# main.net
KiCad netlist of a schematic drawn in EAGLE
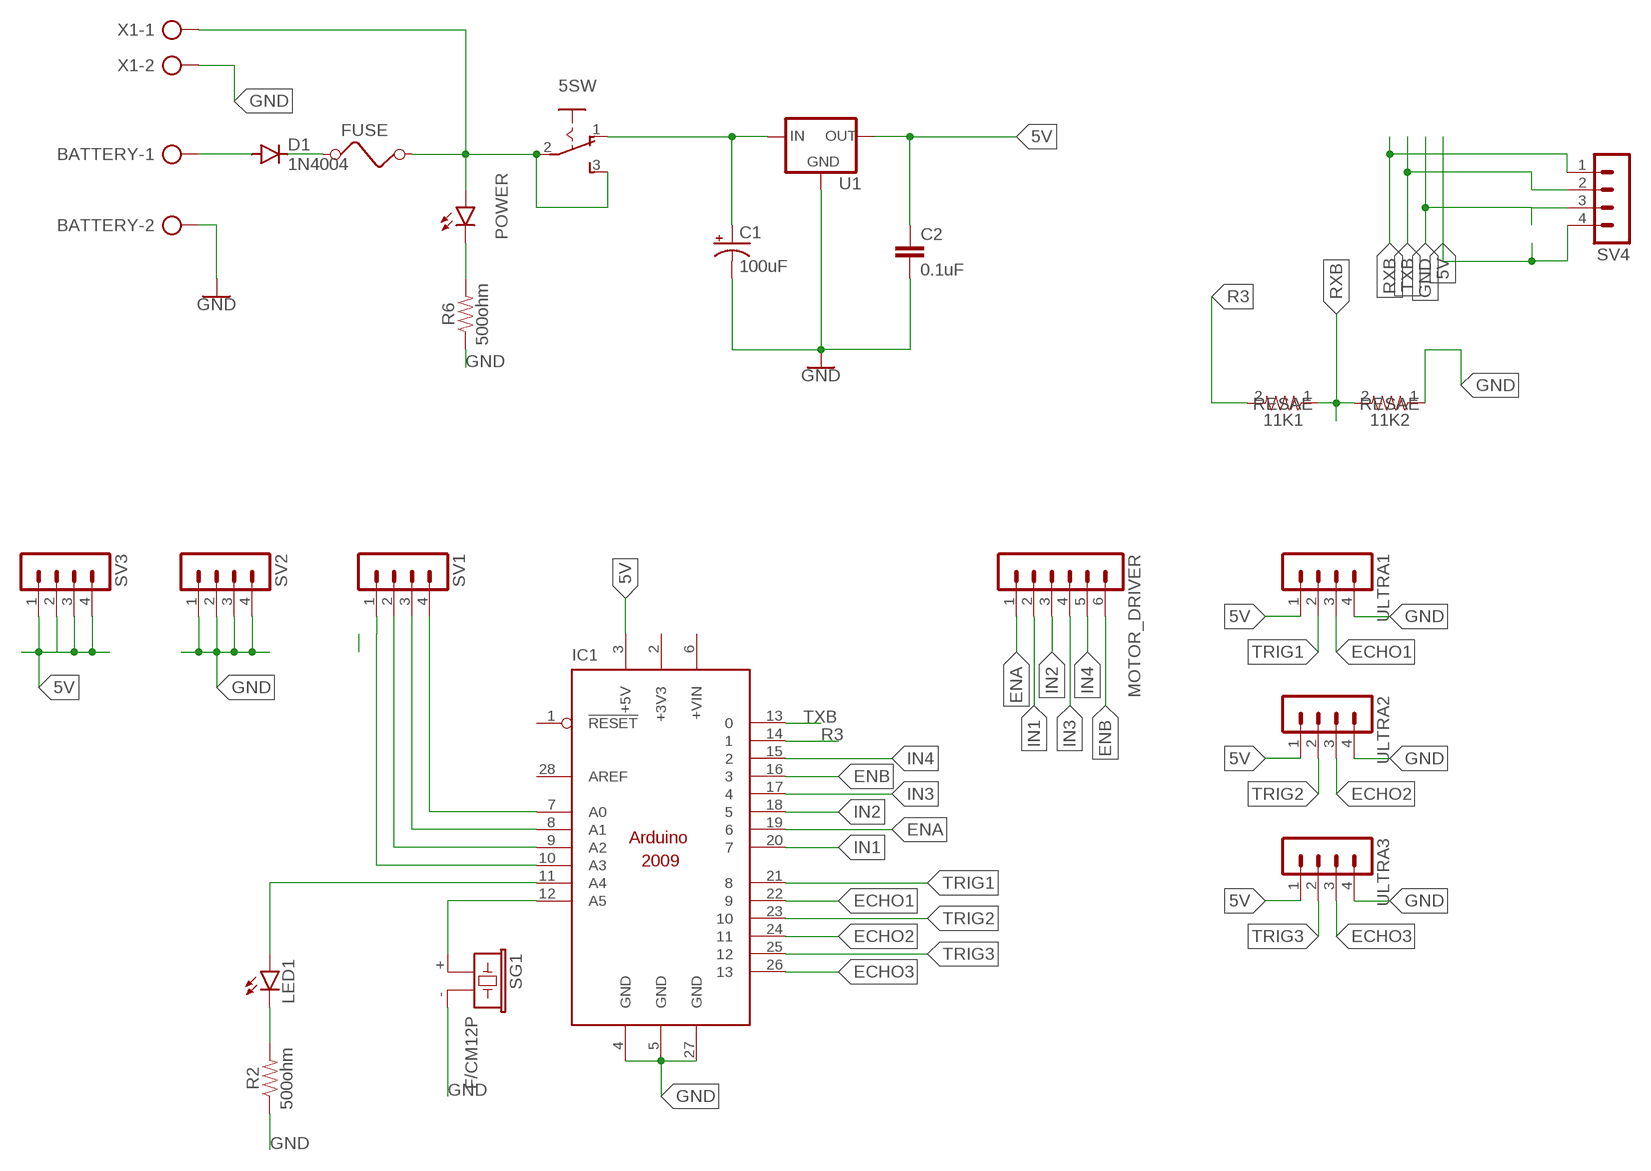
[diagram p0: schematic, sheet 1]

(export (version "E")
  (design (tool "Eeschema 10.0.6"))
  (components
    (comp (ref "5SW")
      (value "255SB")
      (footprint "eagle-import:255SB")
      (libsource (lib "eagle-import") (part "255SB"))
    )
    (comp (ref "11K1")
      (value "RESAE")
      (footprint "eagle-import:RESAD846W63L520D250B")
      (libsource (lib "eagle-import") (part "RESAE"))
    )
    (comp (ref "11K2")
      (value "RESAE")
      (footprint "eagle-import:RESAD846W63L520D250B")
      (libsource (lib "eagle-import") (part "RESAE"))
    )
    (comp (ref "BATTERY")
      (value "AK500/2-H")
      (footprint "eagle-import:AK500_2-H")
      (libsource (lib "eagle-import") (part "AK500/2-H"))
    )
    (comp (ref "C1")
      (value "100uF")
      (footprint "eagle-import:CPOL-RADIAL-2.5MM-6.5MM")
      (libsource (lib "eagle-import") (part "100UF-POLAR-RADIAL-2.5MM-25V-20%"))
    )
    (comp (ref "C2")
      (value "0.1uF")
      (footprint "eagle-import:CAP-PTH-SMALL-KIT")
      (libsource (lib "eagle-import") (part "0.1UF-KIT-EZ-50V-20%"))
    )
    (comp (ref "D1")
      (value "1N4004")
      (footprint "eagle-import:DO41-10")
      (libsource (lib "eagle-import") (part "1N4004"))
    )
    (comp (ref "FUSE")
      (value "FUSE")
      (footprint "eagle-import:FUSE")
      (libsource (lib "eagle-import") (part "FUSE"))
    )
    (comp (ref "IC1")
      (value "ARDUINO2009_10")
      (footprint "eagle-import:ARDUINO2009")
      (libsource (lib "eagle-import") (part "ARDUINO2009_10"))
    )
    (comp (ref "LED1")
      (value "LED10MM")
      (footprint "eagle-import:LED10MM")
      (libsource (lib "eagle-import") (part "LED10MM"))
    )
    (comp (ref "MOTOR_DRIVER")
      (value "MA06-1")
      (footprint "eagle-import:MA06-1")
      (libsource (lib "eagle-import") (part "MA06-1"))
    )
    (comp (ref "POWER")
      (value "LED3MM")
      (footprint "eagle-import:LED3MM")
      (libsource (lib "eagle-import") (part "LED3MM"))
    )
    (comp (ref "R2")
      (value "500ohm")
      (footprint "eagle-import:AXIAL-0.3")
      (libsource (lib "eagle-import") (part "10MOHM-HORIZ-1/4W-5%"))
    )
    (comp (ref "R6")
      (value "500ohm")
      (footprint "eagle-import:AXIAL-0.3")
      (libsource (lib "eagle-import") (part "10MOHM-HORIZ-1/4W-5%"))
    )
    (comp (ref "SG1")
      (value "F/CM12P")
      (footprint "eagle-import:F_CM12P")
      (libsource (lib "eagle-import") (part "F/CM12P"))
    )
    (comp (ref "SV1")
      (value "MA04-1")
      (footprint "eagle-import:MA04-1")
      (libsource (lib "eagle-import") (part "MA04-1"))
    )
    (comp (ref "SV2")
      (value "MA04-1")
      (footprint "eagle-import:MA04-1")
      (libsource (lib "eagle-import") (part "MA04-1"))
    )
    (comp (ref "SV3")
      (value "MA04-1")
      (footprint "eagle-import:MA04-1")
      (libsource (lib "eagle-import") (part "MA04-1"))
    )
    (comp (ref "SV4")
      (value "MA04-1")
      (footprint "eagle-import:MA04-1")
      (libsource (lib "eagle-import") (part "MA04-1"))
    )
    (comp (ref "U1")
      (value "78XXS")
      (footprint "eagle-import:78XXS")
      (libsource (lib "eagle-import") (part "78XXS"))
    )
    (comp (ref "ULTRA1")
      (value "MA04-1")
      (footprint "eagle-import:MA04-1")
      (libsource (lib "eagle-import") (part "MA04-1"))
    )
    (comp (ref "ULTRA2")
      (value "MA04-1")
      (footprint "eagle-import:MA04-1")
      (libsource (lib "eagle-import") (part "MA04-1"))
    )
    (comp (ref "ULTRA3")
      (value "MA04-1")
      (footprint "eagle-import:MA04-1")
      (libsource (lib "eagle-import") (part "MA04-1"))
    )
    (comp (ref "X1")
      (value "AK500/2-H")
      (footprint "eagle-import:AK500_2-H")
      (libsource (lib "eagle-import") (part "AK500/2-H"))
    )
  )
  (nets
    (net (code "1") (name "/+3V3") (class "Default")
      (node (ref "IC1") (pin "2") (pinfunction "+3V3_2") (pintype "power_in"))
    )
    (net (code "2") (name "5V") (class "Default")
      (node (ref "C2") (pin "1") (pinfunction "1_1") (pintype "passive"))
      (node (ref "IC1") (pin "3") (pinfunction "+5V_3") (pintype "power_in"))
      (node (ref "SV3") (pin "1") (pinfunction "1_1") (pintype "passive"))
      (node (ref "SV3") (pin "2") (pinfunction "2_2") (pintype "passive"))
      (node (ref "SV3") (pin "3") (pinfunction "3_3") (pintype "passive"))
      (node (ref "SV3") (pin "4") (pinfunction "4_4") (pintype "passive"))
      (node (ref "SV4") (pin "4") (pinfunction "4_4") (pintype "passive"))
      (node (ref "U1") (pin "OUT") (pinfunction "OUT_OUT") (pintype "passive"))
      (node (ref "ULTRA1") (pin "1") (pinfunction "1_1") (pintype "passive"))
      (node (ref "ULTRA2") (pin "1") (pinfunction "1_1") (pintype "passive"))
      (node (ref "ULTRA3") (pin "1") (pinfunction "1_1") (pintype "passive"))
    )
    (net (code "3") (name "ECHO1") (class "Default")
      (node (ref "IC1") (pin "22") (pinfunction "9_22") (pintype "bidirectional"))
      (node (ref "ULTRA1") (pin "3") (pinfunction "3_3") (pintype "passive"))
    )
    (net (code "4") (name "ECHO2") (class "Default")
      (node (ref "IC1") (pin "24") (pinfunction "11_24") (pintype "bidirectional"))
      (node (ref "ULTRA2") (pin "3") (pinfunction "3_3") (pintype "passive"))
    )
    (net (code "5") (name "ECHO3") (class "Default")
      (node (ref "IC1") (pin "26") (pinfunction "13_26") (pintype "bidirectional"))
      (node (ref "ULTRA3") (pin "3") (pinfunction "3_3") (pintype "passive"))
    )
    (net (code "6") (name "ENA") (class "Default")
      (node (ref "IC1") (pin "19") (pinfunction "6_19") (pintype "bidirectional"))
      (node (ref "MOTOR_DRIVER") (pin "1") (pinfunction "1_1") (pintype "passive"))
    )
    (net (code "7") (name "ENB") (class "Default")
      (node (ref "IC1") (pin "16") (pinfunction "3_16") (pintype "bidirectional"))
      (node (ref "MOTOR_DRIVER") (pin "6") (pinfunction "6_6") (pintype "passive"))
    )
    (net (code "8") (name "GND") (class "Default")
      (node (ref "11K2") (pin "1") (pinfunction "1_1") (pintype "passive"))
      (node (ref "BATTERY") (pin "2") (pinfunction "KL_2") (pintype "passive"))
      (node (ref "C1") (pin "2") (pinfunction "-_2") (pintype "passive"))
      (node (ref "C2") (pin "2") (pinfunction "2_2") (pintype "passive"))
      (node (ref "IC1") (pin "27") (pinfunction "GND_27") (pintype "power_in"))
      (node (ref "IC1") (pin "4") (pinfunction "GND_4") (pintype "power_in"))
      (node (ref "IC1") (pin "5") (pinfunction "GND_5") (pintype "power_in"))
      (node (ref "R2") (pin "P$1") (pinfunction "1_P$1") (pintype "passive"))
      (node (ref "R6") (pin "P$1") (pinfunction "1_P$1") (pintype "passive"))
      (node (ref "SG1") (pin "-") (pinfunction "2_-") (pintype "passive"))
      (node (ref "SV2") (pin "1") (pinfunction "1_1") (pintype "passive"))
      (node (ref "SV2") (pin "2") (pinfunction "2_2") (pintype "passive"))
      (node (ref "SV2") (pin "3") (pinfunction "3_3") (pintype "passive"))
      (node (ref "SV2") (pin "4") (pinfunction "4_4") (pintype "passive"))
      (node (ref "SV4") (pin "3") (pinfunction "3_3") (pintype "passive"))
      (node (ref "U1") (pin "GND") (pinfunction "GND_GND") (pintype "input"))
      (node (ref "ULTRA1") (pin "4") (pinfunction "4_4") (pintype "passive"))
      (node (ref "ULTRA2") (pin "4") (pinfunction "4_4") (pintype "passive"))
      (node (ref "ULTRA3") (pin "4") (pinfunction "4_4") (pintype "passive"))
      (node (ref "X1") (pin "2") (pinfunction "KL_2") (pintype "passive"))
    )
    (net (code "9") (name "IN1") (class "Default")
      (node (ref "IC1") (pin "20") (pinfunction "7_20") (pintype "bidirectional"))
      (node (ref "MOTOR_DRIVER") (pin "2") (pinfunction "2_2") (pintype "passive"))
    )
    (net (code "10") (name "IN2") (class "Default")
      (node (ref "IC1") (pin "18") (pinfunction "5_18") (pintype "bidirectional"))
      (node (ref "MOTOR_DRIVER") (pin "3") (pinfunction "3_3") (pintype "passive"))
    )
    (net (code "11") (name "IN3") (class "Default")
      (node (ref "IC1") (pin "17") (pinfunction "4_17") (pintype "bidirectional"))
      (node (ref "MOTOR_DRIVER") (pin "4") (pinfunction "4_4") (pintype "passive"))
    )
    (net (code "12") (name "IN4") (class "Default")
      (node (ref "IC1") (pin "15") (pinfunction "2_15") (pintype "bidirectional"))
      (node (ref "MOTOR_DRIVER") (pin "5") (pinfunction "5_5") (pintype "passive"))
    )
    (net (code "13") (name "Net-(5SW-O)") (class "Default")
      (node (ref "5SW") (pin "1") (pinfunction "O_1") (pintype "passive"))
      (node (ref "C1") (pin "1") (pinfunction "+_1") (pintype "passive"))
      (node (ref "U1") (pin "IN") (pinfunction "IN_IN") (pintype "input"))
    )
    (net (code "14") (name "Net-(5SW-P)") (class "Default")
      (node (ref "5SW") (pin "2") (pinfunction "P_2") (pintype "passive"))
      (node (ref "5SW") (pin "3") (pinfunction "S_3") (pintype "passive"))
      (node (ref "FUSE") (pin "2") (pinfunction "2_2") (pintype "passive"))
      (node (ref "POWER") (pin "A") (pinfunction "A_A") (pintype "passive"))
      (node (ref "X1") (pin "1") (pinfunction "KL_1") (pintype "passive"))
    )
    (net (code "15") (name "Net-(BATTERYA-KL)") (class "Default")
      (node (ref "BATTERY") (pin "1") (pinfunction "KL_1") (pintype "passive"))
      (node (ref "D1") (pin "A") (pinfunction "A_A") (pintype "passive"))
    )
    (net (code "16") (name "Net-(D1-PadC)") (class "Default")
      (node (ref "D1") (pin "C") (pinfunction "C_C") (pintype "passive"))
      (node (ref "FUSE") (pin "1") (pinfunction "1_1") (pintype "passive"))
    )
    (net (code "17") (name "Net-(IC1-A0)") (class "Default")
      (node (ref "IC1") (pin "7") (pinfunction "A0_7") (pintype "bidirectional"))
      (node (ref "SV1") (pin "4") (pinfunction "4_4") (pintype "passive"))
    )
    (net (code "18") (name "Net-(IC1-A1)") (class "Default")
      (node (ref "IC1") (pin "8") (pinfunction "A1_8") (pintype "bidirectional"))
      (node (ref "SV1") (pin "3") (pinfunction "3_3") (pintype "passive"))
    )
    (net (code "19") (name "Net-(IC1-A2)") (class "Default")
      (node (ref "IC1") (pin "9") (pinfunction "A2_9") (pintype "bidirectional"))
      (node (ref "SV1") (pin "2") (pinfunction "2_2") (pintype "passive"))
    )
    (net (code "20") (name "Net-(IC1-A3)") (class "Default")
      (node (ref "IC1") (pin "10") (pinfunction "A3_10") (pintype "bidirectional"))
      (node (ref "SV1") (pin "1") (pinfunction "1_1") (pintype "passive"))
    )
    (net (code "21") (name "Net-(IC1-A4)") (class "Default")
      (node (ref "IC1") (pin "11") (pinfunction "A4_11") (pintype "bidirectional"))
      (node (ref "LED1") (pin "A") (pinfunction "A_A") (pintype "passive"))
    )
    (net (code "22") (name "Net-(IC1-A5)") (class "Default")
      (node (ref "IC1") (pin "12") (pinfunction "A5_12") (pintype "bidirectional"))
      (node (ref "SG1") (pin "+") (pinfunction "1_+") (pintype "passive"))
    )
    (net (code "23") (name "Net-(LED1-C)") (class "Default")
      (node (ref "LED1") (pin "K") (pinfunction "C_K") (pintype "passive"))
      (node (ref "R2") (pin "P$2") (pinfunction "2_P$2") (pintype "passive"))
    )
    (net (code "24") (name "Net-(POWER-C)") (class "Default")
      (node (ref "POWER") (pin "K") (pinfunction "C_K") (pintype "passive"))
      (node (ref "R6") (pin "P$2") (pinfunction "2_P$2") (pintype "passive"))
    )
    (net (code "25") (name "R3") (class "Default")
      (node (ref "11K1") (pin "2") (pinfunction "2_2") (pintype "passive"))
      (node (ref "IC1") (pin "14") (pinfunction "1_14") (pintype "bidirectional"))
    )
    (net (code "26") (name "RXB") (class "Default")
      (node (ref "11K1") (pin "1") (pinfunction "1_1") (pintype "passive"))
      (node (ref "11K2") (pin "2") (pinfunction "2_2") (pintype "passive"))
      (node (ref "SV4") (pin "1") (pinfunction "1_1") (pintype "passive"))
    )
    (net (code "27") (name "TRIG1") (class "Default")
      (node (ref "IC1") (pin "21") (pinfunction "8_21") (pintype "bidirectional"))
      (node (ref "ULTRA1") (pin "2") (pinfunction "2_2") (pintype "passive"))
    )
    (net (code "28") (name "TRIG2") (class "Default")
      (node (ref "IC1") (pin "23") (pinfunction "10_23") (pintype "bidirectional"))
      (node (ref "ULTRA2") (pin "2") (pinfunction "2_2") (pintype "passive"))
    )
    (net (code "29") (name "TRIG3") (class "Default")
      (node (ref "IC1") (pin "25") (pinfunction "12_25") (pintype "bidirectional"))
      (node (ref "ULTRA3") (pin "2") (pinfunction "2_2") (pintype "passive"))
    )
    (net (code "30") (name "TXB") (class "Default")
      (node (ref "IC1") (pin "13") (pinfunction "0_13") (pintype "bidirectional"))
      (node (ref "SV4") (pin "2") (pinfunction "2_2") (pintype "passive"))
    )
    (net (code "31") (name "unconnected-(IC1-+VIN-Pad6)") (class "Default")
      (node (ref "IC1") (pin "6") (pinfunction "+VIN_6") (pintype "bidirectional"))
    )
    (net (code "32") (name "unconnected-(IC1-AREF-Pad28)") (class "Default")
      (node (ref "IC1") (pin "28") (pinfunction "AREF_28") (pintype "bidirectional"))
    )
    (net (code "33") (name "unconnected-(IC1-~{RESET}-Pad1)") (class "Default")
      (node (ref "IC1") (pin "1") (pinfunction "~{RESET}_1") (pintype "bidirectional"))
    )
  )
)
